# Control_Panel_High_Level.net
KiCad netlist of a schematic drawn in EAGLE
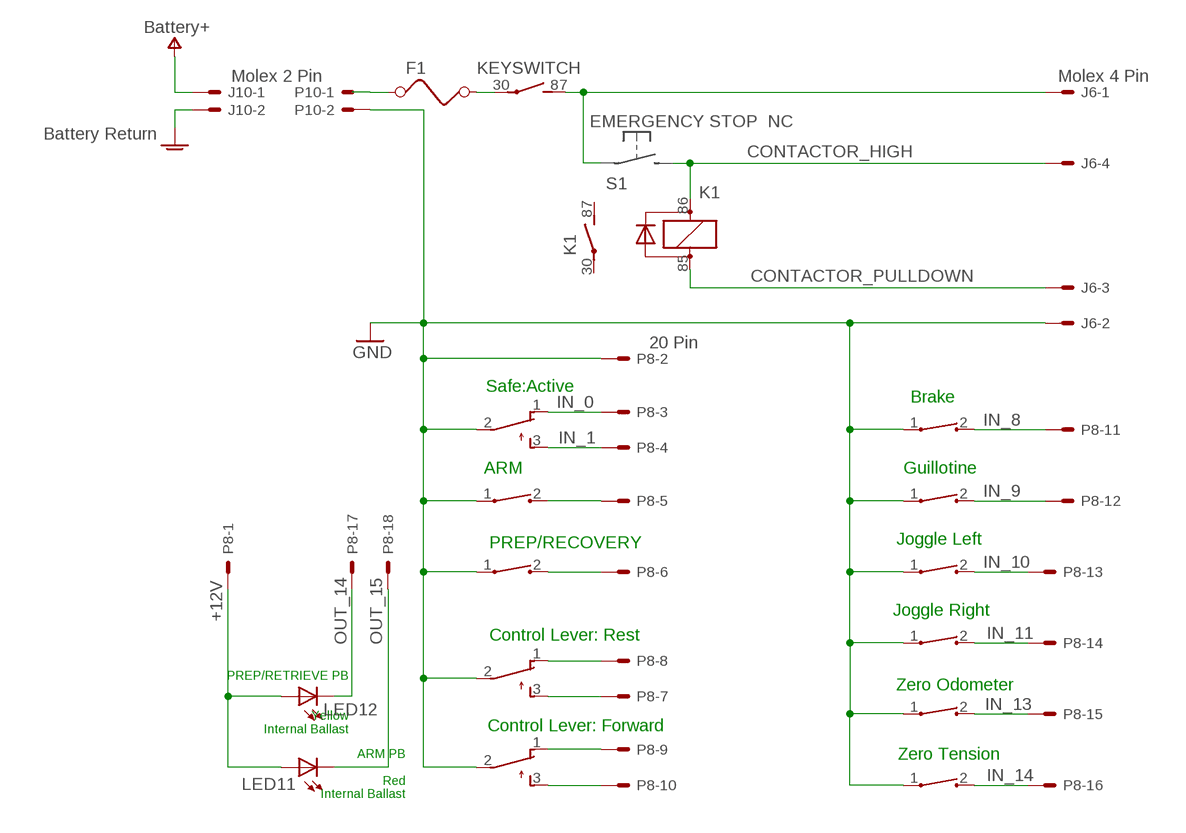
[diagram p0: schematic, sheet 1]

(export (version "E")
  (design (tool "Eeschema 10.0.6"))
  (components
    (comp (ref "F1")
      (value "FUSE")
      (footprint "eagle-import:FUSE")
      (libsource (lib "eagle-import") (part "FUSE"))
    )
    (comp (ref "J6")
      (value "Molex 4 Pin")
      (footprint "eagle-import:22-23-2041")
      (fields (field (name "MF") "MOLEX") (field (name "MPN") "22-23-2041"))
      (libsource (lib "eagle-import") (part "22-23-2041"))
    )
    (comp (ref "J10")
      (value "22-23-2021")
      (footprint "eagle-import:22-23-2021")
      (fields (field (name "MF") "MOLEX"))
      (libsource (lib "eagle-import") (part "22-23-2021"))
    )
    (comp (ref "K1")
      (value "CB1-D-P-12V")
      (footprint "eagle-import:CB1")
      (fields (field (name "MF") "AROMAT/ MATSUSHITA"))
      (libsource (lib "eagle-import") (part "CB1V-D-P-12"))
    )
    (comp (ref "KEYSWITCH")
      (value "Starter Relay")
      (footprint "eagle-import:CB1")
      (fields (field (name "MF") "AROMAT/ MATSUSHITA") (field (name "MPN") "CB1A-P-12V"))
      (libsource (lib "eagle-import") (part "CB1A-P-12V"))
    )
    (comp (ref "LED11")
      (value "LED5MM")
      (footprint "eagle-import:LED5MM")
      (libsource (lib "eagle-import") (part "LED5MM"))
    )
    (comp (ref "LED12")
      (value "LED5MM")
      (footprint "eagle-import:LED5MM")
      (libsource (lib "eagle-import") (part "LED5MM"))
    )
    (comp (ref "P8")
      (value "20 Pin")
      (footprint "eagle-import:70543-20")
      (libsource (lib "eagle-import") (part "C-GRID-20-70543"))
    )
    (comp (ref "P10")
      (value "Molex 2 Pin")
      (footprint "eagle-import:22-23-2021")
      (fields (field (name "MF") "MOLEX") (field (name "MPN") "22-23-2021"))
      (libsource (lib "eagle-import") (part "22-23-2021"))
    )
    (comp (ref "S2")
      (value "TL32PO")
      (footprint "eagle-import:TL3XPO")
      (libsource (lib "eagle-import") (part "TL32PO"))
    )
    (comp (ref "S3")
      (value "TL32PO")
      (footprint "eagle-import:TL3XPO")
      (libsource (lib "eagle-import") (part "TL32PO"))
    )
    (comp (ref "S8")
      (value "TL32PO")
      (footprint "eagle-import:TL3XPO")
      (libsource (lib "eagle-import") (part "TL32PO"))
    )
    (comp (ref "SW1")
      (value "CT10-XXXX-A2")
      (footprint "eagle-import:CT10-XXXX-A2")
      (libsource (lib "eagle-import") (part "CT10-XXXX-A2"))
    )
    (comp (ref "SW2")
      (value "CT10-XXXX-A2")
      (footprint "eagle-import:CT10-XXXX-A2")
      (libsource (lib "eagle-import") (part "CT10-XXXX-A2"))
    )
    (comp (ref "SW3")
      (value "CT10-XXXX-A2")
      (footprint "eagle-import:CT10-XXXX-A2")
      (libsource (lib "eagle-import") (part "CT10-XXXX-A2"))
    )
    (comp (ref "SW4")
      (value "CT10-XXXX-A2")
      (footprint "eagle-import:CT10-XXXX-A2")
      (libsource (lib "eagle-import") (part "CT10-XXXX-A2"))
    )
    (comp (ref "SW7")
      (value "CT10-XXXX-A2")
      (footprint "eagle-import:CT10-XXXX-A2")
      (libsource (lib "eagle-import") (part "CT10-XXXX-A2"))
    )
    (comp (ref "SW8")
      (value "CT10-XXXX-A2")
      (footprint "eagle-import:CT10-XXXX-A2")
      (libsource (lib "eagle-import") (part "CT10-XXXX-A2"))
    )
    (comp (ref "SW9")
      (value "CT10-XXXX-A2")
      (footprint "eagle-import:CT10-XXXX-A2")
      (libsource (lib "eagle-import") (part "CT10-XXXX-A2"))
    )
    (comp (ref "SW10")
      (value "CT10-XXXX-A2")
      (footprint "eagle-import:CT10-XXXX-A2")
      (libsource (lib "eagle-import") (part "CT10-XXXX-A2"))
    )
  )
  (nets
    (net (code "1") (name "/+12V") (class "Default")
      (node (ref "LED11") (pin "A") (pinfunction "A_A") (pintype "passive"))
      (node (ref "LED12") (pin "A") (pinfunction "A_A") (pintype "passive"))
      (node (ref "P8") (pin "1") (pinfunction "S_1") (pintype "passive"))
    )
    (net (code "2") (name "/CONTACTOR_HIGH") (class "Default")
      (node (ref "J6") (pin "4") (pinfunction "S_4") (pintype "passive"))
      (node (ref "K1") (pin "86") (pinfunction "+_86") (pintype "passive"))
    )
    (net (code "3") (name "/CONTACTOR_PULLDOWN") (class "Default")
      (node (ref "J6") (pin "3") (pinfunction "S_3") (pintype "passive"))
      (node (ref "K1") (pin "85") (pinfunction "-_85") (pintype "passive"))
    )
    (net (code "4") (name "/IN_0") (class "Default")
      (node (ref "P8") (pin "3") (pinfunction "S_3") (pintype "passive"))
      (node (ref "S8") (pin "1") (pinfunction "O_1") (pintype "passive"))
    )
    (net (code "5") (name "/IN_1") (class "Default")
      (node (ref "P8") (pin "4") (pinfunction "S_4") (pintype "passive"))
      (node (ref "S8") (pin "3") (pinfunction "S_3") (pintype "passive"))
    )
    (net (code "6") (name "/IN_8") (class "Default")
      (node (ref "P8") (pin "11") (pinfunction "S_11") (pintype "passive"))
      (node (ref "SW7") (pin "2") (pinfunction "2_2") (pintype "passive"))
    )
    (net (code "7") (name "/IN_9") (class "Default")
      (node (ref "P8") (pin "12") (pinfunction "S_12") (pintype "passive"))
      (node (ref "SW8") (pin "2") (pinfunction "2_2") (pintype "passive"))
    )
    (net (code "8") (name "/IN_10") (class "Default")
      (node (ref "P8") (pin "13") (pinfunction "S_13") (pintype "passive"))
      (node (ref "SW9") (pin "2") (pinfunction "2_2") (pintype "passive"))
    )
    (net (code "9") (name "/IN_11") (class "Default")
      (node (ref "P8") (pin "14") (pinfunction "S_14") (pintype "passive"))
      (node (ref "SW10") (pin "2") (pinfunction "2_2") (pintype "passive"))
    )
    (net (code "10") (name "/IN_13") (class "Default")
      (node (ref "P8") (pin "15") (pinfunction "S_15") (pintype "passive"))
      (node (ref "SW2") (pin "2") (pinfunction "2_2") (pintype "passive"))
    )
    (net (code "11") (name "/IN_14") (class "Default")
      (node (ref "P8") (pin "16") (pinfunction "S_16") (pintype "passive"))
      (node (ref "SW1") (pin "2") (pinfunction "2_2") (pintype "passive"))
    )
    (net (code "12") (name "/OUT_14") (class "Default")
      (node (ref "LED12") (pin "K") (pinfunction "C_K") (pintype "passive"))
      (node (ref "P8") (pin "17") (pinfunction "S_17") (pintype "passive"))
    )
    (net (code "13") (name "/OUT_15") (class "Default")
      (node (ref "LED11") (pin "K") (pinfunction "C_K") (pintype "passive"))
      (node (ref "P8") (pin "18") (pinfunction "S_18") (pintype "passive"))
    )
    (net (code "14") (name "Battery Return") (class "Default")
      (node (ref "J10") (pin "2") (pinfunction "S_2") (pintype "passive"))
    )
    (net (code "15") (name "Battery+") (class "Default")
      (node (ref "J10") (pin "1") (pinfunction "S_1") (pintype "passive"))
    )
    (net (code "16") (name "GND") (class "Default")
      (node (ref "J6") (pin "2") (pinfunction "S_2") (pintype "passive"))
      (node (ref "P10") (pin "2") (pinfunction "S_2") (pintype "passive"))
      (node (ref "P8") (pin "2") (pinfunction "S_2") (pintype "passive"))
      (node (ref "S2") (pin "2") (pinfunction "P_2") (pintype "passive"))
      (node (ref "S3") (pin "2") (pinfunction "P_2") (pintype "passive"))
      (node (ref "S8") (pin "2") (pinfunction "P_2") (pintype "passive"))
      (node (ref "SW1") (pin "1") (pinfunction "1_1") (pintype "passive"))
      (node (ref "SW10") (pin "1") (pinfunction "1_1") (pintype "passive"))
      (node (ref "SW2") (pin "1") (pinfunction "1_1") (pintype "passive"))
      (node (ref "SW3") (pin "1") (pinfunction "1_1") (pintype "passive"))
      (node (ref "SW4") (pin "1") (pinfunction "1_1") (pintype "passive"))
      (node (ref "SW7") (pin "1") (pinfunction "1_1") (pintype "passive"))
      (node (ref "SW8") (pin "1") (pinfunction "1_1") (pintype "passive"))
      (node (ref "SW9") (pin "1") (pinfunction "1_1") (pintype "passive"))
    )
    (net (code "17") (name "Net-(J6A-S)") (class "Default")
      (node (ref "J6") (pin "1") (pinfunction "S_1") (pintype "passive"))
      (node (ref "KEYSWITCH") (pin "87") (pinfunction "S_87") (pintype "passive"))
    )
    (net (code "18") (name "Net-(KEYSWITCHB-P)") (class "Default")
      (node (ref "F1") (pin "2") (pinfunction "2_2") (pintype "passive"))
      (node (ref "KEYSWITCH") (pin "30") (pinfunction "P_30") (pintype "passive"))
    )
    (net (code "19") (name "Net-(P8B-S)") (class "Default")
      (node (ref "P8") (pin "10") (pinfunction "S_10") (pintype "passive"))
      (node (ref "S3") (pin "3") (pinfunction "S_3") (pintype "passive"))
    )
    (net (code "20") (name "Net-(P8P-S)") (class "Default")
      (node (ref "P8") (pin "5") (pinfunction "S_5") (pintype "passive"))
      (node (ref "SW3") (pin "2") (pinfunction "2_2") (pintype "passive"))
    )
    (net (code "21") (name "Net-(P8Q-S)") (class "Default")
      (node (ref "P8") (pin "6") (pinfunction "S_6") (pintype "passive"))
      (node (ref "SW4") (pin "2") (pinfunction "2_2") (pintype "passive"))
    )
    (net (code "22") (name "Net-(P8R-S)") (class "Default")
      (node (ref "P8") (pin "7") (pinfunction "S_7") (pintype "passive"))
      (node (ref "S2") (pin "3") (pinfunction "S_3") (pintype "passive"))
    )
    (net (code "23") (name "Net-(P8S-S)") (class "Default")
      (node (ref "P8") (pin "8") (pinfunction "S_8") (pintype "passive"))
      (node (ref "S2") (pin "1") (pinfunction "O_1") (pintype "passive"))
    )
    (net (code "24") (name "Net-(P8T-S)") (class "Default")
      (node (ref "P8") (pin "9") (pinfunction "S_9") (pintype "passive"))
      (node (ref "S3") (pin "1") (pinfunction "O_1") (pintype "passive"))
    )
    (net (code "25") (name "Net-(P10A-S)") (class "Default")
      (node (ref "F1") (pin "1") (pinfunction "1_1") (pintype "passive"))
      (node (ref "P10") (pin "1") (pinfunction "S_1") (pintype "passive"))
    )
    (net (code "26") (name "unconnected-(K1B-P-Pad30)") (class "Default")
      (node (ref "K1") (pin "30") (pinfunction "P_30") (pintype "passive"))
    )
    (net (code "27") (name "unconnected-(K1B-S-Pad87)") (class "Default")
      (node (ref "K1") (pin "87") (pinfunction "S_87") (pintype "passive"))
    )
  )
)
